# MCU.net
KiCad netlist of a schematic drawn in EAGLE
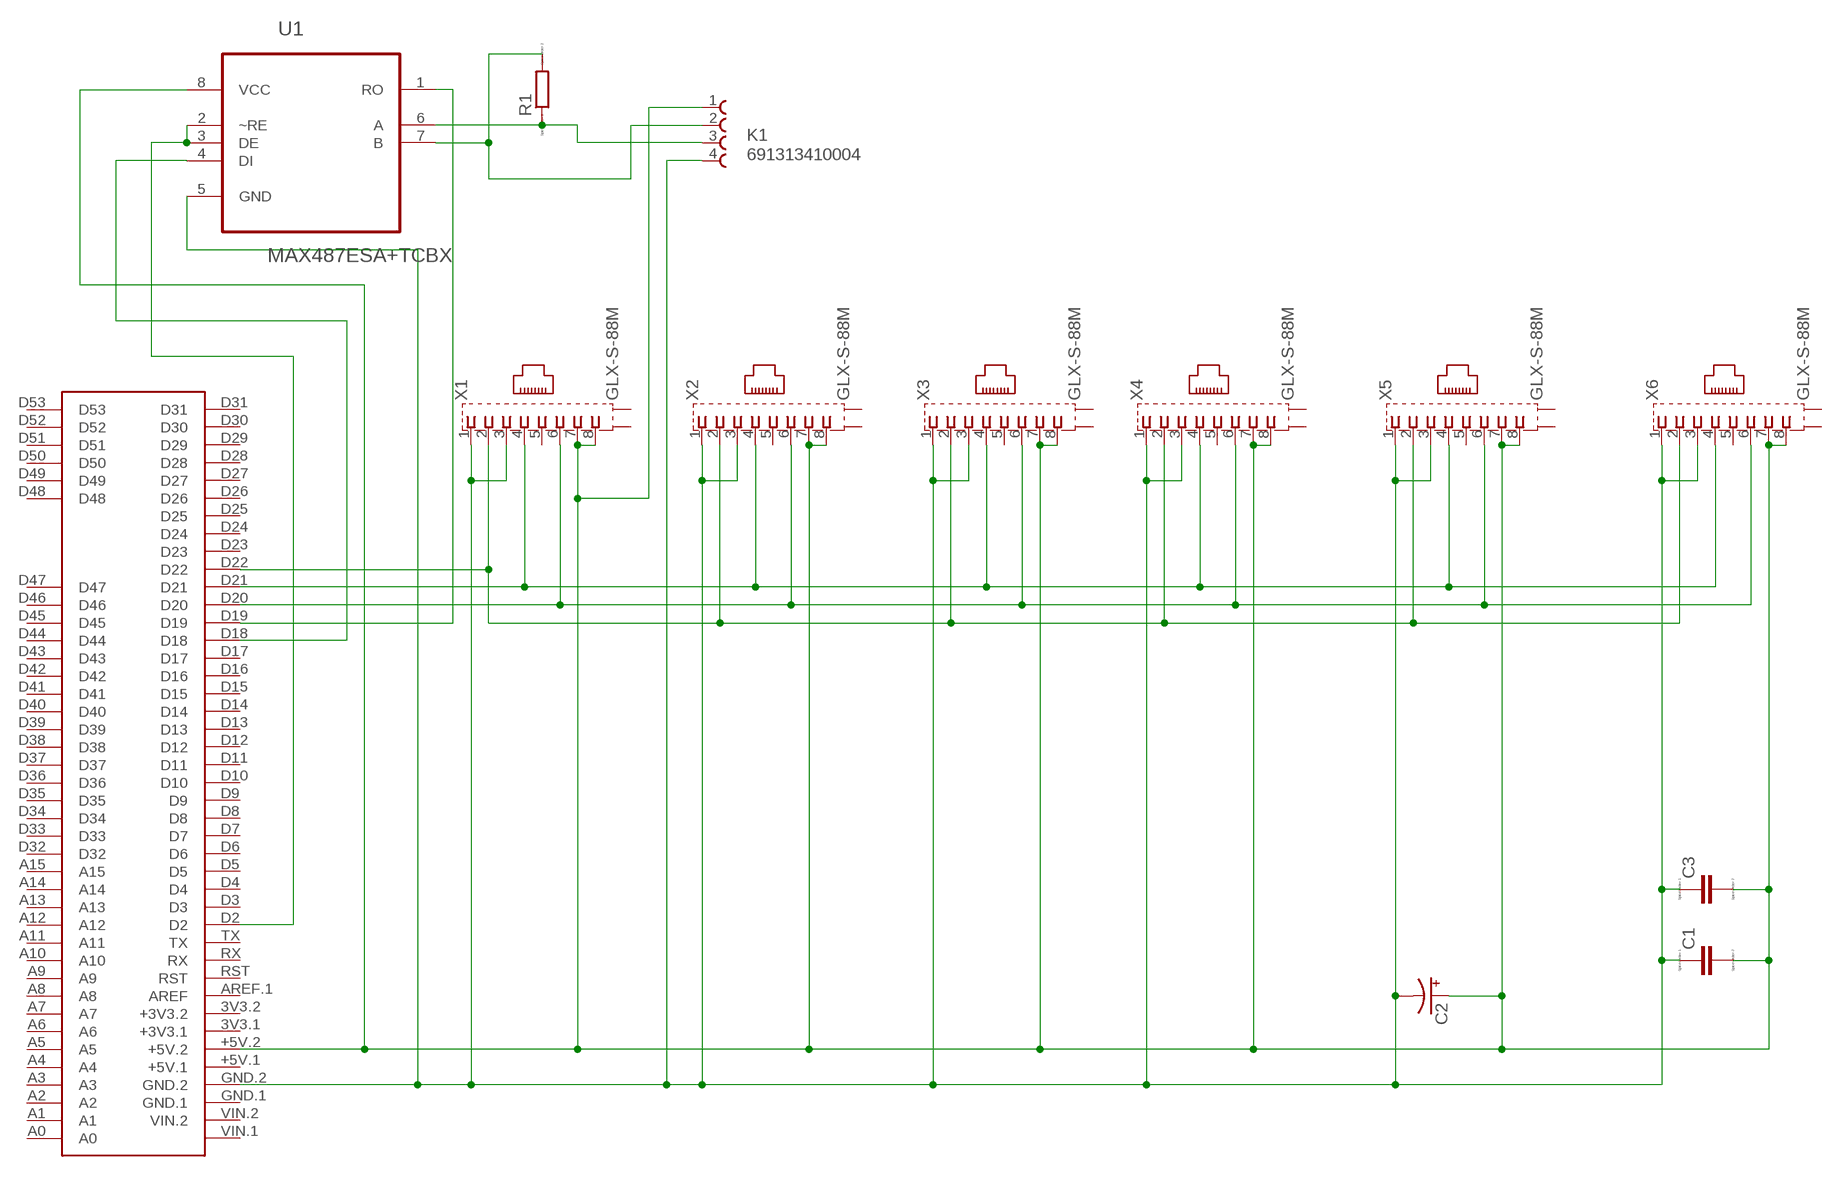
[diagram p0: schematic, sheet 1]

(export (version "E")
  (design (tool "Eeschema 10.0.6"))
  (components
    (comp (ref "C1")
      (value "CC1206")
      (footprint "eagle-import:C1206")
      (libsource (lib "eagle-import") (part "CC1206"))
    )
    (comp (ref "C2")
      (value "CPOL-US153CLV-0807")
      (footprint "eagle-import:153CLV-0807")
      (libsource (lib "eagle-import") (part "CPOL-US153CLV-0807"))
    )
    (comp (ref "C3")
      (value "CC1206")
      (footprint "eagle-import:C1206")
      (libsource (lib "eagle-import") (part "CC1206"))
    )
    (comp (ref "K1")
      (value "691313410004")
      (footprint "eagle-import:691313410004")
      (libsource (lib "eagle-import") (part "691313410004"))
    )
    (comp (ref "R1")
      (value "RR1206")
      (footprint "eagle-import:R1206")
      (libsource (lib "eagle-import") (part "RR1206"))
    )
    (comp (ref "U$1")
      (value "MEGA2560_MIKRO")
      (footprint "eagle-import:MEGA2560_MIKRO")
      (libsource (lib "eagle-import") (part "MEGA2560_MIKRO"))
    )
    (comp (ref "U1")
      (value "MAX487ESA+TCBX")
      (footprint "eagle-import:SOIC127P600X175-8N")
      (fields (field (name "MF") "Maxim Integrated"))
      (libsource (lib "eagle-import") (part "MAX487ESA+TCBX"))
    )
    (comp (ref "X1")
      (value "GLX-S-88M")
      (footprint "eagle-import:GLX-S-88M")
      (libsource (lib "eagle-import") (part "GLX-S-88M"))
    )
    (comp (ref "X2")
      (value "GLX-S-88M")
      (footprint "eagle-import:GLX-S-88M")
      (libsource (lib "eagle-import") (part "GLX-S-88M"))
    )
    (comp (ref "X3")
      (value "GLX-S-88M")
      (footprint "eagle-import:GLX-S-88M")
      (libsource (lib "eagle-import") (part "GLX-S-88M"))
    )
    (comp (ref "X4")
      (value "GLX-S-88M")
      (footprint "eagle-import:GLX-S-88M")
      (libsource (lib "eagle-import") (part "GLX-S-88M"))
    )
    (comp (ref "X5")
      (value "GLX-S-88M")
      (footprint "eagle-import:GLX-S-88M")
      (libsource (lib "eagle-import") (part "GLX-S-88M"))
    )
    (comp (ref "X6")
      (value "GLX-S-88M")
      (footprint "eagle-import:GLX-S-88M")
      (libsource (lib "eagle-import") (part "GLX-S-88M"))
    )
  )
  (nets
    (net (code "1") (name "Net-(U$1-PadD20)") (class "Default")
      (node (ref "U$1") (pin "D20") (pinfunction "D20_D20") (pintype "bidirectional"))
      (node (ref "X1") (pin "6") (pinfunction "6_6") (pintype "passive"))
      (node (ref "X2") (pin "6") (pinfunction "6_6") (pintype "passive"))
      (node (ref "X3") (pin "6") (pinfunction "6_6") (pintype "passive"))
      (node (ref "X4") (pin "6") (pinfunction "6_6") (pintype "passive"))
      (node (ref "X5") (pin "6") (pinfunction "6_6") (pintype "passive"))
      (node (ref "X6") (pin "6") (pinfunction "6_6") (pintype "passive"))
    )
    (net (code "2") (name "Net-(U$1-PadD21)") (class "Default")
      (node (ref "U$1") (pin "D21") (pinfunction "D21_D21") (pintype "bidirectional"))
      (node (ref "X1") (pin "4") (pinfunction "4_4") (pintype "passive"))
      (node (ref "X2") (pin "4") (pinfunction "4_4") (pintype "passive"))
      (node (ref "X3") (pin "4") (pinfunction "4_4") (pintype "passive"))
      (node (ref "X4") (pin "4") (pinfunction "4_4") (pintype "passive"))
      (node (ref "X5") (pin "4") (pinfunction "4_4") (pintype "passive"))
      (node (ref "X6") (pin "4") (pinfunction "4_4") (pintype "passive"))
    )
    (net (code "3") (name "Net-(U$1-PadD22)") (class "Default")
      (node (ref "U$1") (pin "D22") (pinfunction "D22_D22") (pintype "bidirectional"))
      (node (ref "X1") (pin "2") (pinfunction "2_2") (pintype "passive"))
      (node (ref "X2") (pin "2") (pinfunction "2_2") (pintype "passive"))
      (node (ref "X3") (pin "2") (pinfunction "2_2") (pintype "passive"))
      (node (ref "X4") (pin "2") (pinfunction "2_2") (pintype "passive"))
      (node (ref "X5") (pin "2") (pinfunction "2_2") (pintype "passive"))
      (node (ref "X6") (pin "2") (pinfunction "2_2") (pintype "passive"))
    )
    (net (code "4") (name "Net-(U1-A)") (class "Default")
      (node (ref "K1") (pin "3") (pinfunction "3_3") (pintype "passive"))
      (node (ref "R1") (pin "1") (pinfunction "1_1") (pintype "passive"))
      (node (ref "U1") (pin "6") (pinfunction "A_6") (pintype "bidirectional"))
    )
    (net (code "5") (name "Net-(U1-B)") (class "Default")
      (node (ref "K1") (pin "2") (pinfunction "2_2") (pintype "passive"))
      (node (ref "R1") (pin "2") (pinfunction "2_2") (pintype "passive"))
      (node (ref "U1") (pin "7") (pinfunction "B_7") (pintype "bidirectional"))
    )
    (net (code "6") (name "Net-(U1-DE)") (class "Default")
      (node (ref "U$1") (pin "D2") (pinfunction "D2_D2") (pintype "bidirectional"))
      (node (ref "U1") (pin "2") (pinfunction "~{RE}_2") (pintype "input"))
      (node (ref "U1") (pin "3") (pinfunction "DE_3") (pintype "input"))
    )
    (net (code "7") (name "Net-(U1-DI)") (class "Default")
      (node (ref "U$1") (pin "D18") (pinfunction "D18_D18") (pintype "bidirectional"))
      (node (ref "U1") (pin "4") (pinfunction "DI_4") (pintype "input"))
    )
    (net (code "8") (name "Net-(U1-GND)") (class "Default")
      (node (ref "C1") (pin "1") (pinfunction "1_1") (pintype "passive"))
      (node (ref "C2") (pin "-") (pinfunction "-_-") (pintype "passive"))
      (node (ref "C3") (pin "1") (pinfunction "1_1") (pintype "passive"))
      (node (ref "K1") (pin "4") (pinfunction "4_4") (pintype "passive"))
      (node (ref "U$1") (pin "GND.2") (pinfunction "GND.2_GND.2") (pintype "bidirectional"))
      (node (ref "U1") (pin "5") (pinfunction "GND_5") (pintype "passive"))
      (node (ref "X1") (pin "1") (pinfunction "1_1") (pintype "passive"))
      (node (ref "X1") (pin "3") (pinfunction "3_3") (pintype "passive"))
      (node (ref "X2") (pin "1") (pinfunction "1_1") (pintype "passive"))
      (node (ref "X2") (pin "3") (pinfunction "3_3") (pintype "passive"))
      (node (ref "X3") (pin "1") (pinfunction "1_1") (pintype "passive"))
      (node (ref "X3") (pin "3") (pinfunction "3_3") (pintype "passive"))
      (node (ref "X4") (pin "1") (pinfunction "1_1") (pintype "passive"))
      (node (ref "X4") (pin "3") (pinfunction "3_3") (pintype "passive"))
      (node (ref "X5") (pin "1") (pinfunction "1_1") (pintype "passive"))
      (node (ref "X5") (pin "3") (pinfunction "3_3") (pintype "passive"))
      (node (ref "X6") (pin "1") (pinfunction "1_1") (pintype "passive"))
      (node (ref "X6") (pin "3") (pinfunction "3_3") (pintype "passive"))
    )
    (net (code "9") (name "Net-(U1-RO)") (class "Default")
      (node (ref "U$1") (pin "D19") (pinfunction "D19_D19") (pintype "bidirectional"))
      (node (ref "U1") (pin "1") (pinfunction "RO_1") (pintype "output"))
    )
    (net (code "10") (name "Net-(U1-VCC)") (class "Default")
      (node (ref "C1") (pin "2") (pinfunction "2_2") (pintype "passive"))
      (node (ref "C2") (pin "+") (pinfunction "+_+") (pintype "passive"))
      (node (ref "C3") (pin "2") (pinfunction "2_2") (pintype "passive"))
      (node (ref "K1") (pin "1") (pinfunction "1_1") (pintype "passive"))
      (node (ref "U$1") (pin "+5V.2") (pinfunction "+5V.2_+5V.2") (pintype "bidirectional"))
      (node (ref "U1") (pin "8") (pinfunction "VCC_8") (pintype "power_in"))
      (node (ref "X1") (pin "7") (pinfunction "7_7") (pintype "passive"))
      (node (ref "X1") (pin "8") (pinfunction "8_8") (pintype "passive"))
      (node (ref "X2") (pin "7") (pinfunction "7_7") (pintype "passive"))
      (node (ref "X2") (pin "8") (pinfunction "8_8") (pintype "passive"))
      (node (ref "X3") (pin "7") (pinfunction "7_7") (pintype "passive"))
      (node (ref "X3") (pin "8") (pinfunction "8_8") (pintype "passive"))
      (node (ref "X4") (pin "7") (pinfunction "7_7") (pintype "passive"))
      (node (ref "X4") (pin "8") (pinfunction "8_8") (pintype "passive"))
      (node (ref "X5") (pin "7") (pinfunction "7_7") (pintype "passive"))
      (node (ref "X5") (pin "8") (pinfunction "8_8") (pintype "passive"))
      (node (ref "X6") (pin "7") (pinfunction "7_7") (pintype "passive"))
      (node (ref "X6") (pin "8") (pinfunction "8_8") (pintype "passive"))
    )
    (net (code "11") (name "unconnected-(U$1-+3V3.1-Pad3V3.1)") (class "Default")
      (node (ref "U$1") (pin "3V3.1") (pinfunction "+3V3.1_3V3.1") (pintype "bidirectional"))
    )
    (net (code "12") (name "unconnected-(U$1-+3V3.2-Pad3V3.2)") (class "Default")
      (node (ref "U$1") (pin "3V3.2") (pinfunction "+3V3.2_3V3.2") (pintype "bidirectional"))
    )
    (net (code "13") (name "unconnected-(U$1-AREF-PadAREF.1)") (class "Default")
      (node (ref "U$1") (pin "AREF.1") (pinfunction "AREF_AREF.1") (pintype "bidirectional"))
    )
    (net (code "14") (name "unconnected-(U$1-Pad+5V.1)") (class "Default")
      (node (ref "U$1") (pin "+5V.1") (pinfunction "+5V.1_+5V.1") (pintype "bidirectional"))
    )
    (net (code "15") (name "unconnected-(U$1-PadA0)") (class "Default")
      (node (ref "U$1") (pin "A0") (pinfunction "A0_A0") (pintype "bidirectional"))
    )
    (net (code "16") (name "unconnected-(U$1-PadA1)") (class "Default")
      (node (ref "U$1") (pin "A1") (pinfunction "A1_A1") (pintype "bidirectional"))
    )
    (net (code "17") (name "unconnected-(U$1-PadA2)") (class "Default")
      (node (ref "U$1") (pin "A2") (pinfunction "A2_A2") (pintype "bidirectional"))
    )
    (net (code "18") (name "unconnected-(U$1-PadA3)") (class "Default")
      (node (ref "U$1") (pin "A3") (pinfunction "A3_A3") (pintype "bidirectional"))
    )
    (net (code "19") (name "unconnected-(U$1-PadA4)") (class "Default")
      (node (ref "U$1") (pin "A4") (pinfunction "A4_A4") (pintype "bidirectional"))
    )
    (net (code "20") (name "unconnected-(U$1-PadA5)") (class "Default")
      (node (ref "U$1") (pin "A5") (pinfunction "A5_A5") (pintype "bidirectional"))
    )
    (net (code "21") (name "unconnected-(U$1-PadA6)") (class "Default")
      (node (ref "U$1") (pin "A6") (pinfunction "A6_A6") (pintype "bidirectional"))
    )
    (net (code "22") (name "unconnected-(U$1-PadA7)") (class "Default")
      (node (ref "U$1") (pin "A7") (pinfunction "A7_A7") (pintype "bidirectional"))
    )
    (net (code "23") (name "unconnected-(U$1-PadA8)") (class "Default")
      (node (ref "U$1") (pin "A8") (pinfunction "A8_A8") (pintype "bidirectional"))
    )
    (net (code "24") (name "unconnected-(U$1-PadA9)") (class "Default")
      (node (ref "U$1") (pin "A9") (pinfunction "A9_A9") (pintype "bidirectional"))
    )
    (net (code "25") (name "unconnected-(U$1-PadA10)") (class "Default")
      (node (ref "U$1") (pin "A10") (pinfunction "A10_A10") (pintype "bidirectional"))
    )
    (net (code "26") (name "unconnected-(U$1-PadA11)") (class "Default")
      (node (ref "U$1") (pin "A11") (pinfunction "A11_A11") (pintype "bidirectional"))
    )
    (net (code "27") (name "unconnected-(U$1-PadA12)") (class "Default")
      (node (ref "U$1") (pin "A12") (pinfunction "A12_A12") (pintype "bidirectional"))
    )
    (net (code "28") (name "unconnected-(U$1-PadA13)") (class "Default")
      (node (ref "U$1") (pin "A13") (pinfunction "A13_A13") (pintype "bidirectional"))
    )
    (net (code "29") (name "unconnected-(U$1-PadA14)") (class "Default")
      (node (ref "U$1") (pin "A14") (pinfunction "A14_A14") (pintype "bidirectional"))
    )
    (net (code "30") (name "unconnected-(U$1-PadA15)") (class "Default")
      (node (ref "U$1") (pin "A15") (pinfunction "A15_A15") (pintype "bidirectional"))
    )
    (net (code "31") (name "unconnected-(U$1-PadD3)") (class "Default")
      (node (ref "U$1") (pin "D3") (pinfunction "D3_D3") (pintype "bidirectional"))
    )
    (net (code "32") (name "unconnected-(U$1-PadD4)") (class "Default")
      (node (ref "U$1") (pin "D4") (pinfunction "D4_D4") (pintype "bidirectional"))
    )
    (net (code "33") (name "unconnected-(U$1-PadD5)") (class "Default")
      (node (ref "U$1") (pin "D5") (pinfunction "D5_D5") (pintype "bidirectional"))
    )
    (net (code "34") (name "unconnected-(U$1-PadD6)") (class "Default")
      (node (ref "U$1") (pin "D6") (pinfunction "D6_D6") (pintype "bidirectional"))
    )
    (net (code "35") (name "unconnected-(U$1-PadD7)") (class "Default")
      (node (ref "U$1") (pin "D7") (pinfunction "D7_D7") (pintype "bidirectional"))
    )
    (net (code "36") (name "unconnected-(U$1-PadD8)") (class "Default")
      (node (ref "U$1") (pin "D8") (pinfunction "D8_D8") (pintype "bidirectional"))
    )
    (net (code "37") (name "unconnected-(U$1-PadD9)") (class "Default")
      (node (ref "U$1") (pin "D9") (pinfunction "D9_D9") (pintype "bidirectional"))
    )
    (net (code "38") (name "unconnected-(U$1-PadD10)") (class "Default")
      (node (ref "U$1") (pin "D10") (pinfunction "D10_D10") (pintype "bidirectional"))
    )
    (net (code "39") (name "unconnected-(U$1-PadD11)") (class "Default")
      (node (ref "U$1") (pin "D11") (pinfunction "D11_D11") (pintype "bidirectional"))
    )
    (net (code "40") (name "unconnected-(U$1-PadD12)") (class "Default")
      (node (ref "U$1") (pin "D12") (pinfunction "D12_D12") (pintype "bidirectional"))
    )
    (net (code "41") (name "unconnected-(U$1-PadD13)") (class "Default")
      (node (ref "U$1") (pin "D13") (pinfunction "D13_D13") (pintype "bidirectional"))
    )
    (net (code "42") (name "unconnected-(U$1-PadD14)") (class "Default")
      (node (ref "U$1") (pin "D14") (pinfunction "D14_D14") (pintype "bidirectional"))
    )
    (net (code "43") (name "unconnected-(U$1-PadD15)") (class "Default")
      (node (ref "U$1") (pin "D15") (pinfunction "D15_D15") (pintype "bidirectional"))
    )
    (net (code "44") (name "unconnected-(U$1-PadD16)") (class "Default")
      (node (ref "U$1") (pin "D16") (pinfunction "D16_D16") (pintype "bidirectional"))
    )
    (net (code "45") (name "unconnected-(U$1-PadD17)") (class "Default")
      (node (ref "U$1") (pin "D17") (pinfunction "D17_D17") (pintype "bidirectional"))
    )
    (net (code "46") (name "unconnected-(U$1-PadD23)") (class "Default")
      (node (ref "U$1") (pin "D23") (pinfunction "D23_D23") (pintype "bidirectional"))
    )
    (net (code "47") (name "unconnected-(U$1-PadD24)") (class "Default")
      (node (ref "U$1") (pin "D24") (pinfunction "D24_D24") (pintype "bidirectional"))
    )
    (net (code "48") (name "unconnected-(U$1-PadD25)") (class "Default")
      (node (ref "U$1") (pin "D25") (pinfunction "D25_D25") (pintype "bidirectional"))
    )
    (net (code "49") (name "unconnected-(U$1-PadD26)") (class "Default")
      (node (ref "U$1") (pin "D26") (pinfunction "D26_D26") (pintype "bidirectional"))
    )
    (net (code "50") (name "unconnected-(U$1-PadD27)") (class "Default")
      (node (ref "U$1") (pin "D27") (pinfunction "D27_D27") (pintype "bidirectional"))
    )
    (net (code "51") (name "unconnected-(U$1-PadD28)") (class "Default")
      (node (ref "U$1") (pin "D28") (pinfunction "D28_D28") (pintype "bidirectional"))
    )
    (net (code "52") (name "unconnected-(U$1-PadD29)") (class "Default")
      (node (ref "U$1") (pin "D29") (pinfunction "D29_D29") (pintype "bidirectional"))
    )
    (net (code "53") (name "unconnected-(U$1-PadD30)") (class "Default")
      (node (ref "U$1") (pin "D30") (pinfunction "D30_D30") (pintype "bidirectional"))
    )
    (net (code "54") (name "unconnected-(U$1-PadD31)") (class "Default")
      (node (ref "U$1") (pin "D31") (pinfunction "D31_D31") (pintype "bidirectional"))
    )
    (net (code "55") (name "unconnected-(U$1-PadD32)") (class "Default")
      (node (ref "U$1") (pin "D32") (pinfunction "D32_D32") (pintype "bidirectional"))
    )
    (net (code "56") (name "unconnected-(U$1-PadD33)") (class "Default")
      (node (ref "U$1") (pin "D33") (pinfunction "D33_D33") (pintype "bidirectional"))
    )
    (net (code "57") (name "unconnected-(U$1-PadD34)") (class "Default")
      (node (ref "U$1") (pin "D34") (pinfunction "D34_D34") (pintype "bidirectional"))
    )
    (net (code "58") (name "unconnected-(U$1-PadD35)") (class "Default")
      (node (ref "U$1") (pin "D35") (pinfunction "D35_D35") (pintype "bidirectional"))
    )
    (net (code "59") (name "unconnected-(U$1-PadD36)") (class "Default")
      (node (ref "U$1") (pin "D36") (pinfunction "D36_D36") (pintype "bidirectional"))
    )
    (net (code "60") (name "unconnected-(U$1-PadD37)") (class "Default")
      (node (ref "U$1") (pin "D37") (pinfunction "D37_D37") (pintype "bidirectional"))
    )
    (net (code "61") (name "unconnected-(U$1-PadD38)") (class "Default")
      (node (ref "U$1") (pin "D38") (pinfunction "D38_D38") (pintype "bidirectional"))
    )
    (net (code "62") (name "unconnected-(U$1-PadD39)") (class "Default")
      (node (ref "U$1") (pin "D39") (pinfunction "D39_D39") (pintype "bidirectional"))
    )
    (net (code "63") (name "unconnected-(U$1-PadD40)") (class "Default")
      (node (ref "U$1") (pin "D40") (pinfunction "D40_D40") (pintype "bidirectional"))
    )
    (net (code "64") (name "unconnected-(U$1-PadD41)") (class "Default")
      (node (ref "U$1") (pin "D41") (pinfunction "D41_D41") (pintype "bidirectional"))
    )
    (net (code "65") (name "unconnected-(U$1-PadD42)") (class "Default")
      (node (ref "U$1") (pin "D42") (pinfunction "D42_D42") (pintype "bidirectional"))
    )
    (net (code "66") (name "unconnected-(U$1-PadD43)") (class "Default")
      (node (ref "U$1") (pin "D43") (pinfunction "D43_D43") (pintype "bidirectional"))
    )
    (net (code "67") (name "unconnected-(U$1-PadD44)") (class "Default")
      (node (ref "U$1") (pin "D44") (pinfunction "D44_D44") (pintype "bidirectional"))
    )
    (net (code "68") (name "unconnected-(U$1-PadD45)") (class "Default")
      (node (ref "U$1") (pin "D45") (pinfunction "D45_D45") (pintype "bidirectional"))
    )
    (net (code "69") (name "unconnected-(U$1-PadD46)") (class "Default")
      (node (ref "U$1") (pin "D46") (pinfunction "D46_D46") (pintype "bidirectional"))
    )
    (net (code "70") (name "unconnected-(U$1-PadD47)") (class "Default")
      (node (ref "U$1") (pin "D47") (pinfunction "D47_D47") (pintype "bidirectional"))
    )
    (net (code "71") (name "unconnected-(U$1-PadD48)") (class "Default")
      (node (ref "U$1") (pin "D48") (pinfunction "D48_D48") (pintype "bidirectional"))
    )
    (net (code "72") (name "unconnected-(U$1-PadD49)") (class "Default")
      (node (ref "U$1") (pin "D49") (pinfunction "D49_D49") (pintype "bidirectional"))
    )
    (net (code "73") (name "unconnected-(U$1-PadD50)") (class "Default")
      (node (ref "U$1") (pin "D50") (pinfunction "D50_D50") (pintype "bidirectional"))
    )
    (net (code "74") (name "unconnected-(U$1-PadD51)") (class "Default")
      (node (ref "U$1") (pin "D51") (pinfunction "D51_D51") (pintype "bidirectional"))
    )
    (net (code "75") (name "unconnected-(U$1-PadD52)") (class "Default")
      (node (ref "U$1") (pin "D52") (pinfunction "D52_D52") (pintype "bidirectional"))
    )
    (net (code "76") (name "unconnected-(U$1-PadD53)") (class "Default")
      (node (ref "U$1") (pin "D53") (pinfunction "D53_D53") (pintype "bidirectional"))
    )
    (net (code "77") (name "unconnected-(U$1-PadGND.1)") (class "Default")
      (node (ref "U$1") (pin "GND.1") (pinfunction "GND.1_GND.1") (pintype "bidirectional"))
    )
    (net (code "78") (name "unconnected-(U$1-PadRST)") (class "Default")
      (node (ref "U$1") (pin "RST") (pinfunction "RST_RST") (pintype "bidirectional"))
    )
    (net (code "79") (name "unconnected-(U$1-PadRX)") (class "Default")
      (node (ref "U$1") (pin "RX") (pinfunction "RX_RX") (pintype "bidirectional"))
    )
    (net (code "80") (name "unconnected-(U$1-PadTX)") (class "Default")
      (node (ref "U$1") (pin "TX") (pinfunction "TX_TX") (pintype "bidirectional"))
    )
    (net (code "81") (name "unconnected-(U$1-PadVIN.1)") (class "Default")
      (node (ref "U$1") (pin "VIN.1") (pinfunction "VIN.1_VIN.1") (pintype "bidirectional"))
    )
    (net (code "82") (name "unconnected-(U$1-PadVIN.2)") (class "Default")
      (node (ref "U$1") (pin "VIN.2") (pinfunction "VIN.2_VIN.2") (pintype "bidirectional"))
    )
    (net (code "83") (name "unconnected-(X1-Pad5)") (class "Default")
      (node (ref "X1") (pin "5") (pinfunction "5_5") (pintype "passive"))
    )
    (net (code "84") (name "unconnected-(X1-PadS1)") (class "Default")
      (node (ref "X1") (pin "S1") (pinfunction "S1_S1") (pintype "passive"))
    )
    (net (code "85") (name "unconnected-(X1-PadS2)") (class "Default")
      (node (ref "X1") (pin "S2") (pinfunction "S2_S2") (pintype "passive"))
    )
    (net (code "86") (name "unconnected-(X2-Pad5)") (class "Default")
      (node (ref "X2") (pin "5") (pinfunction "5_5") (pintype "passive"))
    )
    (net (code "87") (name "unconnected-(X2-PadS1)") (class "Default")
      (node (ref "X2") (pin "S1") (pinfunction "S1_S1") (pintype "passive"))
    )
    (net (code "88") (name "unconnected-(X2-PadS2)") (class "Default")
      (node (ref "X2") (pin "S2") (pinfunction "S2_S2") (pintype "passive"))
    )
    (net (code "89") (name "unconnected-(X3-Pad5)") (class "Default")
      (node (ref "X3") (pin "5") (pinfunction "5_5") (pintype "passive"))
    )
    (net (code "90") (name "unconnected-(X3-PadS1)") (class "Default")
      (node (ref "X3") (pin "S1") (pinfunction "S1_S1") (pintype "passive"))
    )
    (net (code "91") (name "unconnected-(X3-PadS2)") (class "Default")
      (node (ref "X3") (pin "S2") (pinfunction "S2_S2") (pintype "passive"))
    )
    (net (code "92") (name "unconnected-(X4-Pad5)") (class "Default")
      (node (ref "X4") (pin "5") (pinfunction "5_5") (pintype "passive"))
    )
    (net (code "93") (name "unconnected-(X4-PadS1)") (class "Default")
      (node (ref "X4") (pin "S1") (pinfunction "S1_S1") (pintype "passive"))
    )
    (net (code "94") (name "unconnected-(X4-PadS2)") (class "Default")
      (node (ref "X4") (pin "S2") (pinfunction "S2_S2") (pintype "passive"))
    )
    (net (code "95") (name "unconnected-(X5-Pad5)") (class "Default")
      (node (ref "X5") (pin "5") (pinfunction "5_5") (pintype "passive"))
    )
    (net (code "96") (name "unconnected-(X5-PadS1)") (class "Default")
      (node (ref "X5") (pin "S1") (pinfunction "S1_S1") (pintype "passive"))
    )
    (net (code "97") (name "unconnected-(X5-PadS2)") (class "Default")
      (node (ref "X5") (pin "S2") (pinfunction "S2_S2") (pintype "passive"))
    )
    (net (code "98") (name "unconnected-(X6-Pad5)") (class "Default")
      (node (ref "X6") (pin "5") (pinfunction "5_5") (pintype "passive"))
    )
    (net (code "99") (name "unconnected-(X6-PadS1)") (class "Default")
      (node (ref "X6") (pin "S1") (pinfunction "S1_S1") (pintype "passive"))
    )
    (net (code "100") (name "unconnected-(X6-PadS2)") (class "Default")
      (node (ref "X6") (pin "S2") (pinfunction "S2_S2") (pintype "passive"))
    )
  )
)
